# water_monitor.net
KiCad netlist of a schematic drawn in EAGLE
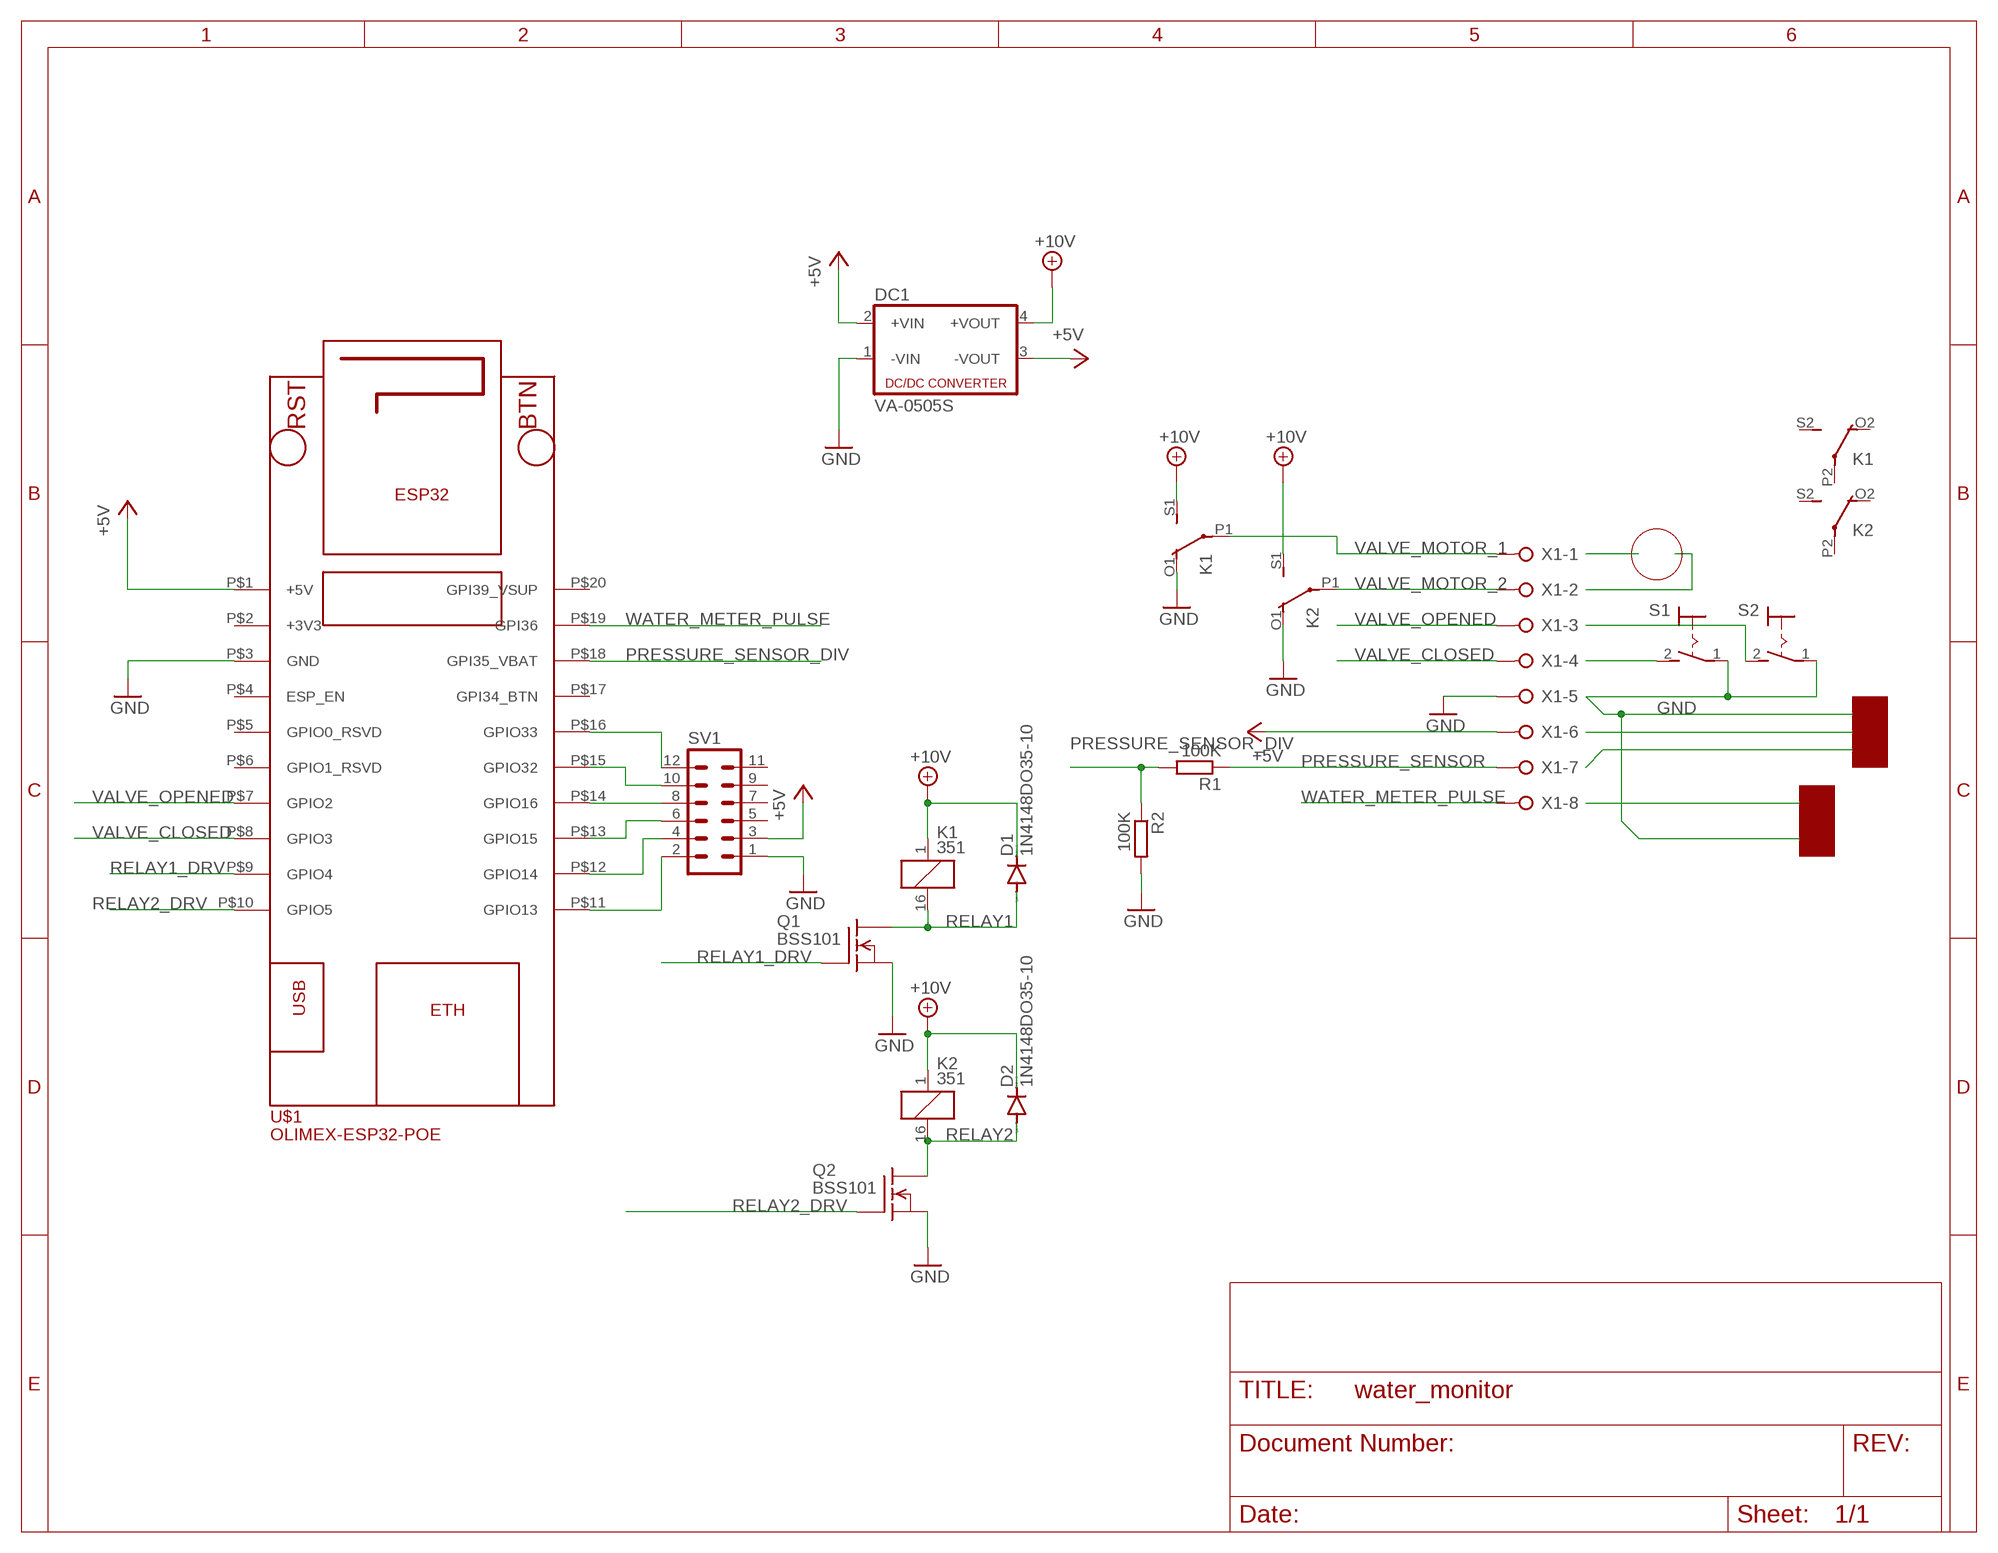
[diagram p0: schematic, sheet 1]

(export (version "E")
  (design (tool "Eeschema 10.0.6"))
  (components
    (comp (ref "D1")
      (value "1N4148DO35-10")
      (footprint "eagle-import:DO35-10")
      (libsource (lib "eagle-import") (part "1N4148DO35-10"))
    )
    (comp (ref "D2")
      (value "1N4148DO35-10")
      (footprint "eagle-import:DO35-10")
      (libsource (lib "eagle-import") (part "1N4148DO35-10"))
    )
    (comp (ref "DC1")
      (value "VA-0505S")
      (footprint "eagle-import:4SIL")
      (libsource (lib "eagle-import") (part "VA-?S0505"))
    )
    (comp (ref "K1")
      (value "351")
      (footprint "eagle-import:351")
      (libsource (lib "eagle-import") (part "351"))
    )
    (comp (ref "K2")
      (value "351")
      (footprint "eagle-import:351")
      (libsource (lib "eagle-import") (part "351"))
    )
    (comp (ref "Q1")
      (value "BSS101")
      (footprint "eagle-import:TO92")
      (libsource (lib "eagle-import") (part "BSS101"))
    )
    (comp (ref "Q2")
      (value "BSS101")
      (footprint "eagle-import:TO92")
      (libsource (lib "eagle-import") (part "BSS101"))
    )
    (comp (ref "R1")
      (value "100K")
      (footprint "eagle-import:0207_10")
      (libsource (lib "eagle-import") (part "R-EU_0207/10"))
    )
    (comp (ref "R2")
      (value "100K")
      (footprint "eagle-import:0207_10")
      (libsource (lib "eagle-import") (part "R-EU_0207/10"))
    )
    (comp (ref "S1")
      (value "MS243")
      (footprint "eagle-import:MS243")
      (libsource (lib "eagle-import") (part "MS243"))
    )
    (comp (ref "S2")
      (value "MS243")
      (footprint "eagle-import:MS243")
      (libsource (lib "eagle-import") (part "MS243"))
    )
    (comp (ref "SV1")
      (value "MA06-2")
      (footprint "eagle-import:MA06-2")
      (libsource (lib "eagle-import") (part "MA06-2"))
    )
    (comp (ref "U$1")
      (value "OLIMEX-ESP32-POE")
      (footprint "eagle-import:OLIMEX-ESP32-POE")
      (libsource (lib "eagle-import") (part "OLIMEX-ESP32-POE"))
    )
    (comp (ref "X1")
      (value "W237-08P")
      (footprint "eagle-import:W237-8P")
      (libsource (lib "eagle-import") (part "W237-08P"))
    )
  )
  (nets
    (net (code "1") (name "+5V") (class "Default")
      (node (ref "DC1") (pin "2") (pinfunction "+VIN_2") (pintype "passive"))
      (node (ref "DC1") (pin "3") (pinfunction "-VOUT_3") (pintype "passive"))
      (node (ref "SV1") (pin "3") (pinfunction "3_3") (pintype "passive"))
      (node (ref "U$1") (pin "P$1") (pinfunction "+5V_P$1") (pintype "power_in"))
      (node (ref "X1") (pin "6") (pinfunction "KL_6") (pintype "passive"))
    )
    (net (code "2") (name "+10V") (class "Default")
      (node (ref "D1") (pin "C") (pinfunction "C_C") (pintype "passive"))
      (node (ref "D2") (pin "C") (pinfunction "C_C") (pintype "passive"))
      (node (ref "DC1") (pin "4") (pinfunction "+VOUT_4") (pintype "passive"))
      (node (ref "K1") (pin "1") (pinfunction "1_1") (pintype "passive"))
      (node (ref "K1") (pin "S1") (pinfunction "S_S1") (pintype "passive"))
      (node (ref "K2") (pin "1") (pinfunction "1_1") (pintype "passive"))
      (node (ref "K2") (pin "S1") (pinfunction "S_S1") (pintype "passive"))
    )
    (net (code "3") (name "/+3V3") (class "Default")
      (node (ref "U$1") (pin "P$2") (pinfunction "+3V3_P$2") (pintype "power_in"))
    )
    (net (code "4") (name "/PRESSURE_SENSOR") (class "Default")
      (node (ref "R1") (pin "1") (pinfunction "1_1") (pintype "passive"))
      (node (ref "X1") (pin "7") (pinfunction "KL_7") (pintype "passive"))
    )
    (net (code "5") (name "/PRESSURE_SENSOR_DIV") (class "Default")
      (node (ref "R1") (pin "2") (pinfunction "2_2") (pintype "passive"))
      (node (ref "R2") (pin "1") (pinfunction "1_1") (pintype "passive"))
      (node (ref "U$1") (pin "P$18") (pinfunction "GPI35_VBAT_P$18") (pintype "input"))
    )
    (net (code "6") (name "/RELAY1") (class "Default")
      (node (ref "D1") (pin "A") (pinfunction "A_A") (pintype "passive"))
      (node (ref "K1") (pin "16") (pinfunction "2_16") (pintype "passive"))
      (node (ref "Q1") (pin "3") (pinfunction "D_3") (pintype "passive"))
    )
    (net (code "7") (name "/RELAY1_DRV") (class "Default")
      (node (ref "Q1") (pin "2") (pinfunction "G_2") (pintype "passive"))
      (node (ref "U$1") (pin "P$9") (pinfunction "GPIO4_P$9") (pintype "bidirectional"))
    )
    (net (code "8") (name "/RELAY2") (class "Default")
      (node (ref "D2") (pin "A") (pinfunction "A_A") (pintype "passive"))
      (node (ref "K2") (pin "16") (pinfunction "2_16") (pintype "passive"))
      (node (ref "Q2") (pin "3") (pinfunction "D_3") (pintype "passive"))
    )
    (net (code "9") (name "/RELAY2_DRV") (class "Default")
      (node (ref "Q2") (pin "2") (pinfunction "G_2") (pintype "passive"))
      (node (ref "U$1") (pin "P$10") (pinfunction "GPIO5_P$10") (pintype "bidirectional"))
    )
    (net (code "10") (name "/VALVE_CLOSED") (class "Default")
      (node (ref "U$1") (pin "P$8") (pinfunction "GPIO3_P$8") (pintype "bidirectional"))
      (node (ref "X1") (pin "4") (pinfunction "KL_4") (pintype "passive"))
    )
    (net (code "11") (name "/VALVE_MOTOR_1") (class "Default")
      (node (ref "K1") (pin "P1") (pinfunction "P_P1") (pintype "passive"))
      (node (ref "X1") (pin "1") (pinfunction "KL_1") (pintype "passive"))
    )
    (net (code "12") (name "/VALVE_MOTOR_2") (class "Default")
      (node (ref "K2") (pin "P1") (pinfunction "P_P1") (pintype "passive"))
      (node (ref "X1") (pin "2") (pinfunction "KL_2") (pintype "passive"))
    )
    (net (code "13") (name "/VALVE_OPENED") (class "Default")
      (node (ref "U$1") (pin "P$7") (pinfunction "GPIO2_P$7") (pintype "bidirectional"))
      (node (ref "X1") (pin "3") (pinfunction "KL_3") (pintype "passive"))
    )
    (net (code "14") (name "/WATER_METER_PULSE") (class "Default")
      (node (ref "U$1") (pin "P$19") (pinfunction "GPI36_P$19") (pintype "input"))
      (node (ref "X1") (pin "8") (pinfunction "KL_8") (pintype "passive"))
    )
    (net (code "15") (name "GND") (class "Default")
      (node (ref "DC1") (pin "1") (pinfunction "-VIN_1") (pintype "passive"))
      (node (ref "K1") (pin "O1") (pinfunction "O_O1") (pintype "passive"))
      (node (ref "K2") (pin "O1") (pinfunction "O_O1") (pintype "passive"))
      (node (ref "Q1") (pin "1") (pinfunction "S_1") (pintype "passive"))
      (node (ref "Q2") (pin "1") (pinfunction "S_1") (pintype "passive"))
      (node (ref "R2") (pin "2") (pinfunction "2_2") (pintype "passive"))
      (node (ref "S1") (pin "1") (pinfunction "P_1") (pintype "passive"))
      (node (ref "S2") (pin "1") (pinfunction "P_1") (pintype "passive"))
      (node (ref "SV1") (pin "1") (pinfunction "1_1") (pintype "passive"))
      (node (ref "U$1") (pin "P$3") (pinfunction "GND_P$3") (pintype "power_in"))
      (node (ref "X1") (pin "5") (pinfunction "KL_5") (pintype "passive"))
    )
    (net (code "16") (name "Net-(U$1-GPIO13)") (class "Default")
      (node (ref "SV1") (pin "2") (pinfunction "2_2") (pintype "passive"))
      (node (ref "U$1") (pin "P$11") (pinfunction "GPIO13_P$11") (pintype "bidirectional"))
    )
    (net (code "17") (name "Net-(U$1-GPIO14)") (class "Default")
      (node (ref "SV1") (pin "4") (pinfunction "4_4") (pintype "passive"))
      (node (ref "U$1") (pin "P$12") (pinfunction "GPIO14_P$12") (pintype "bidirectional"))
    )
    (net (code "18") (name "Net-(U$1-GPIO15)") (class "Default")
      (node (ref "SV1") (pin "6") (pinfunction "6_6") (pintype "passive"))
      (node (ref "U$1") (pin "P$13") (pinfunction "GPIO15_P$13") (pintype "bidirectional"))
    )
    (net (code "19") (name "Net-(U$1-GPIO16)") (class "Default")
      (node (ref "SV1") (pin "8") (pinfunction "8_8") (pintype "passive"))
      (node (ref "U$1") (pin "P$14") (pinfunction "GPIO16_P$14") (pintype "bidirectional"))
    )
    (net (code "20") (name "Net-(U$1-GPIO32)") (class "Default")
      (node (ref "SV1") (pin "10") (pinfunction "10_10") (pintype "passive"))
      (node (ref "U$1") (pin "P$15") (pinfunction "GPIO32_P$15") (pintype "bidirectional"))
    )
    (net (code "21") (name "Net-(U$1-GPIO33)") (class "Default")
      (node (ref "SV1") (pin "12") (pinfunction "12_12") (pintype "passive"))
      (node (ref "U$1") (pin "P$16") (pinfunction "GPIO33_P$16") (pintype "bidirectional"))
    )
    (net (code "22") (name "unconnected-(K1C-O-PadO2)") (class "Default")
      (node (ref "K1") (pin "O2") (pinfunction "O_O2") (pintype "passive"))
    )
    (net (code "23") (name "unconnected-(K1C-P-PadP2)") (class "Default")
      (node (ref "K1") (pin "P2") (pinfunction "P_P2") (pintype "passive"))
    )
    (net (code "24") (name "unconnected-(K1C-S-PadS2)") (class "Default")
      (node (ref "K1") (pin "S2") (pinfunction "S_S2") (pintype "passive"))
    )
    (net (code "25") (name "unconnected-(K2C-O-PadO2)") (class "Default")
      (node (ref "K2") (pin "O2") (pinfunction "O_O2") (pintype "passive"))
    )
    (net (code "26") (name "unconnected-(K2C-P-PadP2)") (class "Default")
      (node (ref "K2") (pin "P2") (pinfunction "P_P2") (pintype "passive"))
    )
    (net (code "27") (name "unconnected-(K2C-S-PadS2)") (class "Default")
      (node (ref "K2") (pin "S2") (pinfunction "S_S2") (pintype "passive"))
    )
    (net (code "28") (name "unconnected-(S1-S-Pad2)") (class "Default")
      (node (ref "S1") (pin "2") (pinfunction "S_2") (pintype "passive"))
    )
    (net (code "29") (name "unconnected-(S2-S-Pad2)") (class "Default")
      (node (ref "S2") (pin "2") (pinfunction "S_2") (pintype "passive"))
    )
    (net (code "30") (name "unconnected-(SV1-Pad5)") (class "Default")
      (node (ref "SV1") (pin "5") (pinfunction "5_5") (pintype "passive"))
    )
    (net (code "31") (name "unconnected-(SV1-Pad7)") (class "Default")
      (node (ref "SV1") (pin "7") (pinfunction "7_7") (pintype "passive"))
    )
    (net (code "32") (name "unconnected-(SV1-Pad9)") (class "Default")
      (node (ref "SV1") (pin "9") (pinfunction "9_9") (pintype "passive"))
    )
    (net (code "33") (name "unconnected-(SV1-Pad11)") (class "Default")
      (node (ref "SV1") (pin "11") (pinfunction "11_11") (pintype "passive"))
    )
    (net (code "34") (name "unconnected-(U$1-ESP_EN-PadP$4)") (class "Default")
      (node (ref "U$1") (pin "P$4") (pinfunction "ESP_EN_P$4") (pintype "input"))
    )
    (net (code "35") (name "unconnected-(U$1-GPI34_BTN-PadP$17)") (class "Default")
      (node (ref "U$1") (pin "P$17") (pinfunction "GPI34_BTN_P$17") (pintype "input"))
    )
    (net (code "36") (name "unconnected-(U$1-GPI39_VSUP-PadP$20)") (class "Default")
      (node (ref "U$1") (pin "P$20") (pinfunction "GPI39_VSUP_P$20") (pintype "input"))
    )
    (net (code "37") (name "unconnected-(U$1-GPIO0_RSVD-PadP$5)") (class "Default")
      (node (ref "U$1") (pin "P$5") (pinfunction "GPIO0_RSVD_P$5") (pintype "bidirectional"))
    )
    (net (code "38") (name "unconnected-(U$1-GPIO1_RSVD-PadP$6)") (class "Default")
      (node (ref "U$1") (pin "P$6") (pinfunction "GPIO1_RSVD_P$6") (pintype "bidirectional"))
    )
  )
)
